# Reflow_Panel_Rev_B.net
KiCad netlist of a schematic drawn in EAGLE
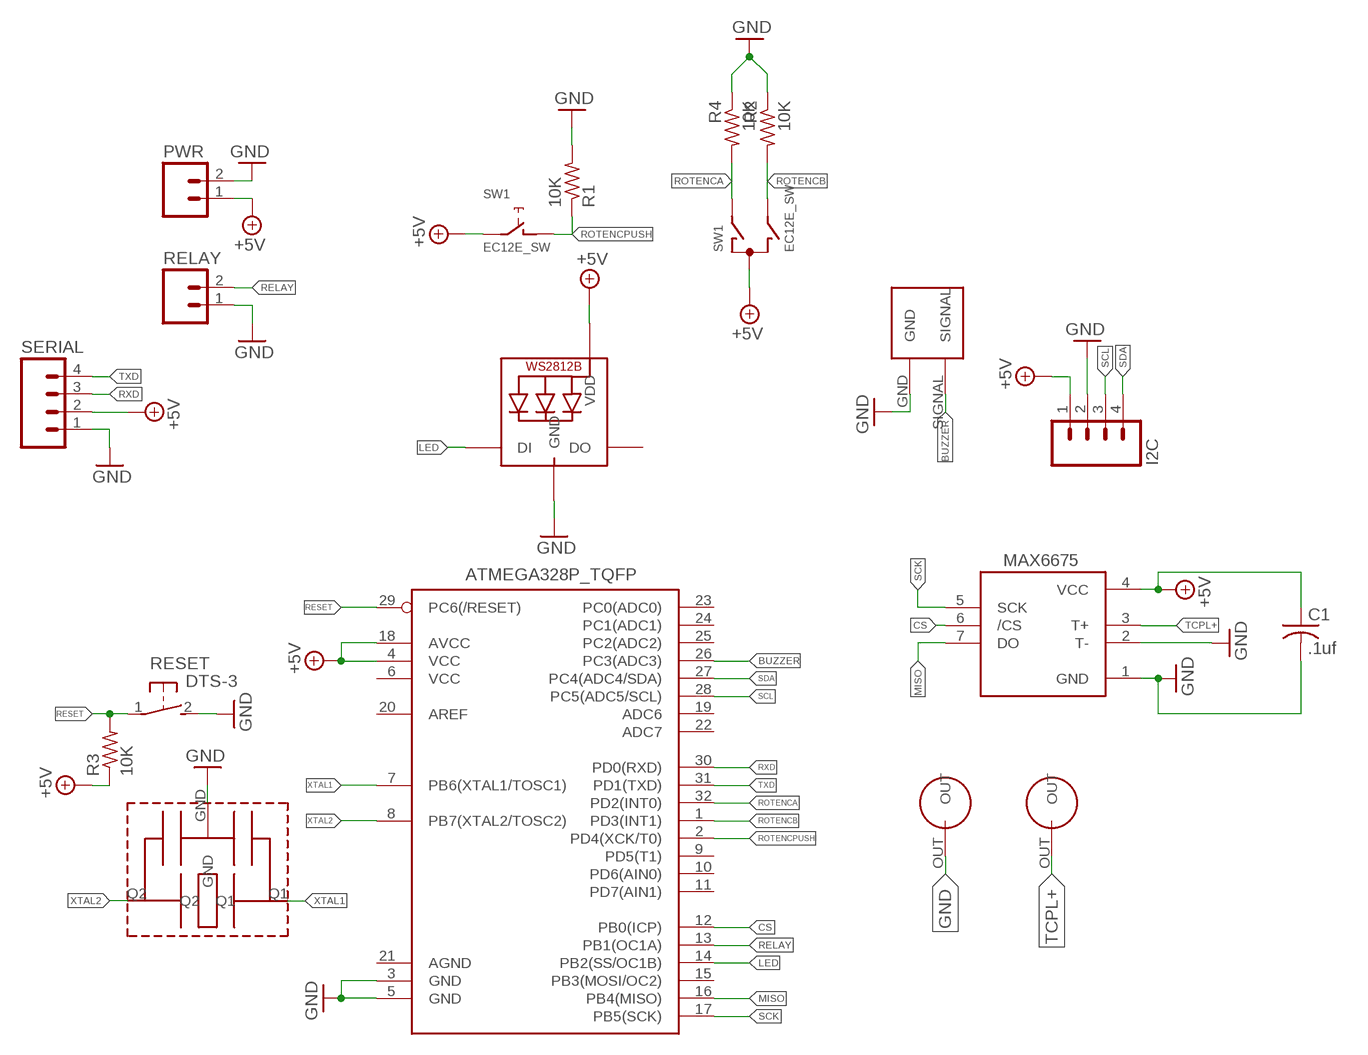
[diagram p0: schematic, sheet 1]

(export (version "E")
  (design (tool "Eeschema 10.0.6"))
  (components
    (comp (ref "C1")
      (value ".1uf")
      (footprint "eagle-import:C0805")
      (libsource (lib "eagle-import") (part "C-USC0805"))
    )
    (comp (ref "I2C")
      (value "M04LOCK_LONGPADS")
      (footprint "eagle-import:1X04_LOCK_LONGPADS")
      (libsource (lib "eagle-import") (part "M04LOCK_LONGPADS"))
    )
    (comp (ref "IC2")
      (value "MAX6675")
      (footprint "eagle-import:SO08")
      (libsource (lib "eagle-import") (part "MAX6675"))
    )
    (comp (ref "LED1")
      (value "WS2812B5050")
      (footprint "eagle-import:WS2812B")
      (libsource (lib "eagle-import") (part "WS2812B5050"))
    )
    (comp (ref "PWR")
      (value "M02LOCK")
      (footprint "eagle-import:1X02_LOCK")
      (libsource (lib "eagle-import") (part "M02LOCK"))
    )
    (comp (ref "R1")
      (value "10K")
      (footprint "eagle-import:M0805")
      (libsource (lib "eagle-import") (part "R-US_M0805"))
    )
    (comp (ref "R2")
      (value "10K")
      (footprint "eagle-import:M0805")
      (libsource (lib "eagle-import") (part "R-US_M0805"))
    )
    (comp (ref "R3")
      (value "10K")
      (footprint "eagle-import:M0805")
      (libsource (lib "eagle-import") (part "R-US_M0805"))
    )
    (comp (ref "R4")
      (value "10K")
      (footprint "eagle-import:M0805")
      (libsource (lib "eagle-import") (part "R-US_M0805"))
    )
    (comp (ref "RELAY")
      (value "M02LOCK")
      (footprint "eagle-import:1X02_LOCK")
      (libsource (lib "eagle-import") (part "M02LOCK"))
    )
    (comp (ref "RESET")
      (value "DTS-3")
      (footprint "eagle-import:DTS-3")
      (libsource (lib "eagle-import") (part "DTS-3"))
    )
    (comp (ref "SERIAL")
      (value "M04LOCK_LONGPADS")
      (footprint "eagle-import:1X04_LOCK_LONGPADS")
      (libsource (lib "eagle-import") (part "M04LOCK_LONGPADS"))
    )
    (comp (ref "SW1")
      (value "EC12E_SW")
      (footprint "eagle-import:ALPS_EC12E_SW")
      (fields (field (name "MPN") "EC12E2424407"))
      (libsource (lib "eagle-import") (part "EC12E_SW"))
    )
    (comp (ref "U$1")
      (value "8.5MMSQUAREBUZZER")
      (footprint "eagle-import:8.5MMSQUAREBUZZER")
      (libsource (lib "eagle-import") (part "8.5MMSQUAREBUZZER"))
    )
    (comp (ref "U$2")
      (value "CSTCE16M0V53-R0")
      (footprint "eagle-import:CSTCE_V13C")
      (libsource (lib "eagle-import") (part "CSTCE16M0V53-R0"))
    )
    (comp (ref "U$3")
      (value "BANANAFEMALE")
      (footprint "eagle-import:BANANAFEMALE")
      (libsource (lib "eagle-import") (part "BANANAFEMALE"))
    )
    (comp (ref "U$4")
      (value "BANANAFEMALE")
      (footprint "eagle-import:BANANAFEMALE")
      (libsource (lib "eagle-import") (part "BANANAFEMALE"))
    )
    (comp (ref "U1")
      (value "ATMEGA328P_TQFP")
      (footprint "eagle-import:TQFP32-08")
      (libsource (lib "eagle-import") (part "ATMEGA328P_TQFP"))
    )
  )
  (nets
    (net (code "1") (name "+5V") (class "Default")
      (node (ref "C1") (pin "1") (pinfunction "1_1") (pintype "passive"))
      (node (ref "I2C") (pin "1") (pinfunction "1_1") (pintype "passive"))
      (node (ref "IC2") (pin "4") (pinfunction "VCC_4") (pintype "power_in"))
      (node (ref "LED1") (pin "1-VDD") (pinfunction "VDD_1-VDD") (pintype "power_in"))
      (node (ref "PWR") (pin "1") (pinfunction "1_1") (pintype "passive"))
      (node (ref "R3") (pin "1") (pinfunction "1_1") (pintype "passive"))
      (node (ref "SERIAL") (pin "2") (pinfunction "2_2") (pintype "passive"))
      (node (ref "SW1") (pin "C") (pinfunction "C_C") (pintype "passive"))
      (node (ref "SW1") (pin "E") (pinfunction "2_E") (pintype "passive"))
      (node (ref "U1") (pin "18") (pinfunction "AVCC_18") (pintype "bidirectional"))
      (node (ref "U1") (pin "4") (pinfunction "VCC_4") (pintype "bidirectional"))
    )
    (net (code "2") (name "BUZZER") (class "Default")
      (node (ref "U$1") (pin "SIGNAL") (pinfunction "SIGNAL_SIGNAL") (pintype "bidirectional"))
      (node (ref "U1") (pin "26") (pinfunction "PC3(ADC3)_26") (pintype "bidirectional"))
    )
    (net (code "3") (name "CS") (class "Default")
      (node (ref "IC2") (pin "6") (pinfunction "/CS_6") (pintype "input"))
      (node (ref "U1") (pin "12") (pinfunction "PB0(ICP)_12") (pintype "bidirectional"))
    )
    (net (code "4") (name "GND") (class "Default")
      (node (ref "C1") (pin "2") (pinfunction "2_2") (pintype "passive"))
      (node (ref "I2C") (pin "2") (pinfunction "2_2") (pintype "passive"))
      (node (ref "IC2") (pin "1") (pinfunction "GND_1") (pintype "power_in"))
      (node (ref "IC2") (pin "2") (pinfunction "T-_2") (pintype "input"))
      (node (ref "LED1") (pin "3-GND") (pinfunction "GND_3-GND") (pintype "power_in"))
      (node (ref "PWR") (pin "2") (pinfunction "2_2") (pintype "passive"))
      (node (ref "R1") (pin "2") (pinfunction "2_2") (pintype "passive"))
      (node (ref "R2") (pin "1") (pinfunction "1_1") (pintype "passive"))
      (node (ref "R4") (pin "1") (pinfunction "1_1") (pintype "passive"))
      (node (ref "RELAY") (pin "1") (pinfunction "1_1") (pintype "passive"))
      (node (ref "RESET") (pin "2") (pinfunction "2_2") (pintype "passive"))
      (node (ref "SERIAL") (pin "1") (pinfunction "1_1") (pintype "passive"))
      (node (ref "U$1") (pin "GND") (pinfunction "GND_GND") (pintype "bidirectional"))
      (node (ref "U$2") (pin "GND") (pinfunction "GND_GND") (pintype "bidirectional"))
      (node (ref "U$3") (pin "OUT") (pinfunction "OUT_OUT") (pintype "bidirectional"))
      (node (ref "U1") (pin "3") (pinfunction "GND_3") (pintype "bidirectional"))
      (node (ref "U1") (pin "5") (pinfunction "GND_5") (pintype "bidirectional"))
    )
    (net (code "5") (name "LED") (class "Default")
      (node (ref "LED1") (pin "4-DIN") (pinfunction "DI_4-DIN") (pintype "input"))
      (node (ref "U1") (pin "14") (pinfunction "PB2(SS/OC1B)_14") (pintype "bidirectional"))
    )
    (net (code "6") (name "MISO") (class "Default")
      (node (ref "IC2") (pin "7") (pinfunction "DO_7") (pintype "output"))
      (node (ref "U1") (pin "16") (pinfunction "PB4(MISO)_16") (pintype "bidirectional"))
    )
    (net (code "7") (name "RELAY") (class "Default")
      (node (ref "RELAY") (pin "2") (pinfunction "2_2") (pintype "passive"))
      (node (ref "U1") (pin "13") (pinfunction "PB1(OC1A)_13") (pintype "bidirectional"))
    )
    (net (code "8") (name "RESET") (class "Default")
      (node (ref "R3") (pin "2") (pinfunction "2_2") (pintype "passive"))
      (node (ref "RESET") (pin "1") (pinfunction "1_1") (pintype "passive"))
      (node (ref "U1") (pin "29") (pinfunction "PC6(/RESET)_29") (pintype "bidirectional"))
    )
    (net (code "9") (name "ROTENCA") (class "Default")
      (node (ref "R4") (pin "2") (pinfunction "2_2") (pintype "passive"))
      (node (ref "SW1") (pin "A") (pinfunction "A_A") (pintype "passive"))
      (node (ref "U1") (pin "32") (pinfunction "PD2(INT0)_32") (pintype "bidirectional"))
    )
    (net (code "10") (name "ROTENCB") (class "Default")
      (node (ref "R2") (pin "2") (pinfunction "2_2") (pintype "passive"))
      (node (ref "SW1") (pin "B") (pinfunction "B_B") (pintype "passive"))
      (node (ref "U1") (pin "1") (pinfunction "PD3(INT1)_1") (pintype "bidirectional"))
    )
    (net (code "11") (name "ROTENCPUSH") (class "Default")
      (node (ref "R1") (pin "1") (pinfunction "1_1") (pintype "passive"))
      (node (ref "SW1") (pin "D") (pinfunction "1_D") (pintype "passive"))
      (node (ref "U1") (pin "2") (pinfunction "PD4(XCK/T0)_2") (pintype "bidirectional"))
    )
    (net (code "12") (name "RXD") (class "Default")
      (node (ref "SERIAL") (pin "3") (pinfunction "3_3") (pintype "passive"))
      (node (ref "U1") (pin "30") (pinfunction "PD0(RXD)_30") (pintype "bidirectional"))
    )
    (net (code "13") (name "SCK") (class "Default")
      (node (ref "IC2") (pin "5") (pinfunction "SCK_5") (pintype "input"))
      (node (ref "U1") (pin "17") (pinfunction "PB5(SCK)_17") (pintype "bidirectional"))
    )
    (net (code "14") (name "SCL") (class "Default")
      (node (ref "I2C") (pin "3") (pinfunction "3_3") (pintype "passive"))
      (node (ref "U1") (pin "28") (pinfunction "PC5(ADC5/SCL)_28") (pintype "bidirectional"))
    )
    (net (code "15") (name "SDA") (class "Default")
      (node (ref "I2C") (pin "4") (pinfunction "4_4") (pintype "passive"))
      (node (ref "U1") (pin "27") (pinfunction "PC4(ADC4/SDA)_27") (pintype "bidirectional"))
    )
    (net (code "16") (name "TCPL+") (class "Default")
      (node (ref "IC2") (pin "3") (pinfunction "T+_3") (pintype "input"))
      (node (ref "U$4") (pin "OUT") (pinfunction "OUT_OUT") (pintype "bidirectional"))
    )
    (net (code "17") (name "TXD") (class "Default")
      (node (ref "SERIAL") (pin "4") (pinfunction "4_4") (pintype "passive"))
      (node (ref "U1") (pin "31") (pinfunction "PD1(TXD)_31") (pintype "bidirectional"))
    )
    (net (code "18") (name "XTAL1") (class "Default")
      (node (ref "U$2") (pin "Q1") (pinfunction "Q1_Q1") (pintype "bidirectional"))
      (node (ref "U1") (pin "7") (pinfunction "PB6(XTAL1/TOSC1)_7") (pintype "bidirectional"))
    )
    (net (code "19") (name "XTAL2") (class "Default")
      (node (ref "U$2") (pin "Q2") (pinfunction "Q2_Q2") (pintype "bidirectional"))
      (node (ref "U1") (pin "8") (pinfunction "PB7(XTAL2/TOSC2)_8") (pintype "bidirectional"))
    )
    (net (code "20") (name "unconnected-(LED1-DO-Pad2-DOUT)") (class "Default")
      (node (ref "LED1") (pin "2-DOUT") (pinfunction "DO_2-DOUT") (pintype "output"))
    )
    (net (code "21") (name "unconnected-(U1-ADC6-Pad19)") (class "Default")
      (node (ref "U1") (pin "19") (pinfunction "ADC6_19") (pintype "bidirectional"))
    )
    (net (code "22") (name "unconnected-(U1-ADC7-Pad22)") (class "Default")
      (node (ref "U1") (pin "22") (pinfunction "ADC7_22") (pintype "bidirectional"))
    )
    (net (code "23") (name "unconnected-(U1-AGND-Pad21)") (class "Default")
      (node (ref "U1") (pin "21") (pinfunction "AGND_21") (pintype "bidirectional"))
    )
    (net (code "24") (name "unconnected-(U1-AREF-Pad20)") (class "Default")
      (node (ref "U1") (pin "20") (pinfunction "AREF_20") (pintype "bidirectional"))
    )
    (net (code "25") (name "unconnected-(U1-PB3(MOSI{slash}OC2)-Pad15)") (class "Default")
      (node (ref "U1") (pin "15") (pinfunction "PB3(MOSI/OC2)_15") (pintype "bidirectional"))
    )
    (net (code "26") (name "unconnected-(U1-PC0(ADC0)-Pad23)") (class "Default")
      (node (ref "U1") (pin "23") (pinfunction "PC0(ADC0)_23") (pintype "bidirectional"))
    )
    (net (code "27") (name "unconnected-(U1-PC1(ADC1)-Pad24)") (class "Default")
      (node (ref "U1") (pin "24") (pinfunction "PC1(ADC1)_24") (pintype "bidirectional"))
    )
    (net (code "28") (name "unconnected-(U1-PC2(ADC2)-Pad25)") (class "Default")
      (node (ref "U1") (pin "25") (pinfunction "PC2(ADC2)_25") (pintype "bidirectional"))
    )
    (net (code "29") (name "unconnected-(U1-PD5(T1)-Pad9)") (class "Default")
      (node (ref "U1") (pin "9") (pinfunction "PD5(T1)_9") (pintype "bidirectional"))
    )
    (net (code "30") (name "unconnected-(U1-PD6(AIN0)-Pad10)") (class "Default")
      (node (ref "U1") (pin "10") (pinfunction "PD6(AIN0)_10") (pintype "bidirectional"))
    )
    (net (code "31") (name "unconnected-(U1-PD7(AIN1)-Pad11)") (class "Default")
      (node (ref "U1") (pin "11") (pinfunction "PD7(AIN1)_11") (pintype "bidirectional"))
    )
    (net (code "32") (name "unconnected-(U1-VCC-Pad6)") (class "Default")
      (node (ref "U1") (pin "6") (pinfunction "VCC_6") (pintype "bidirectional"))
    )
  )
)
